# DigitalIO.net
KiCad netlist of a schematic drawn in EAGLE
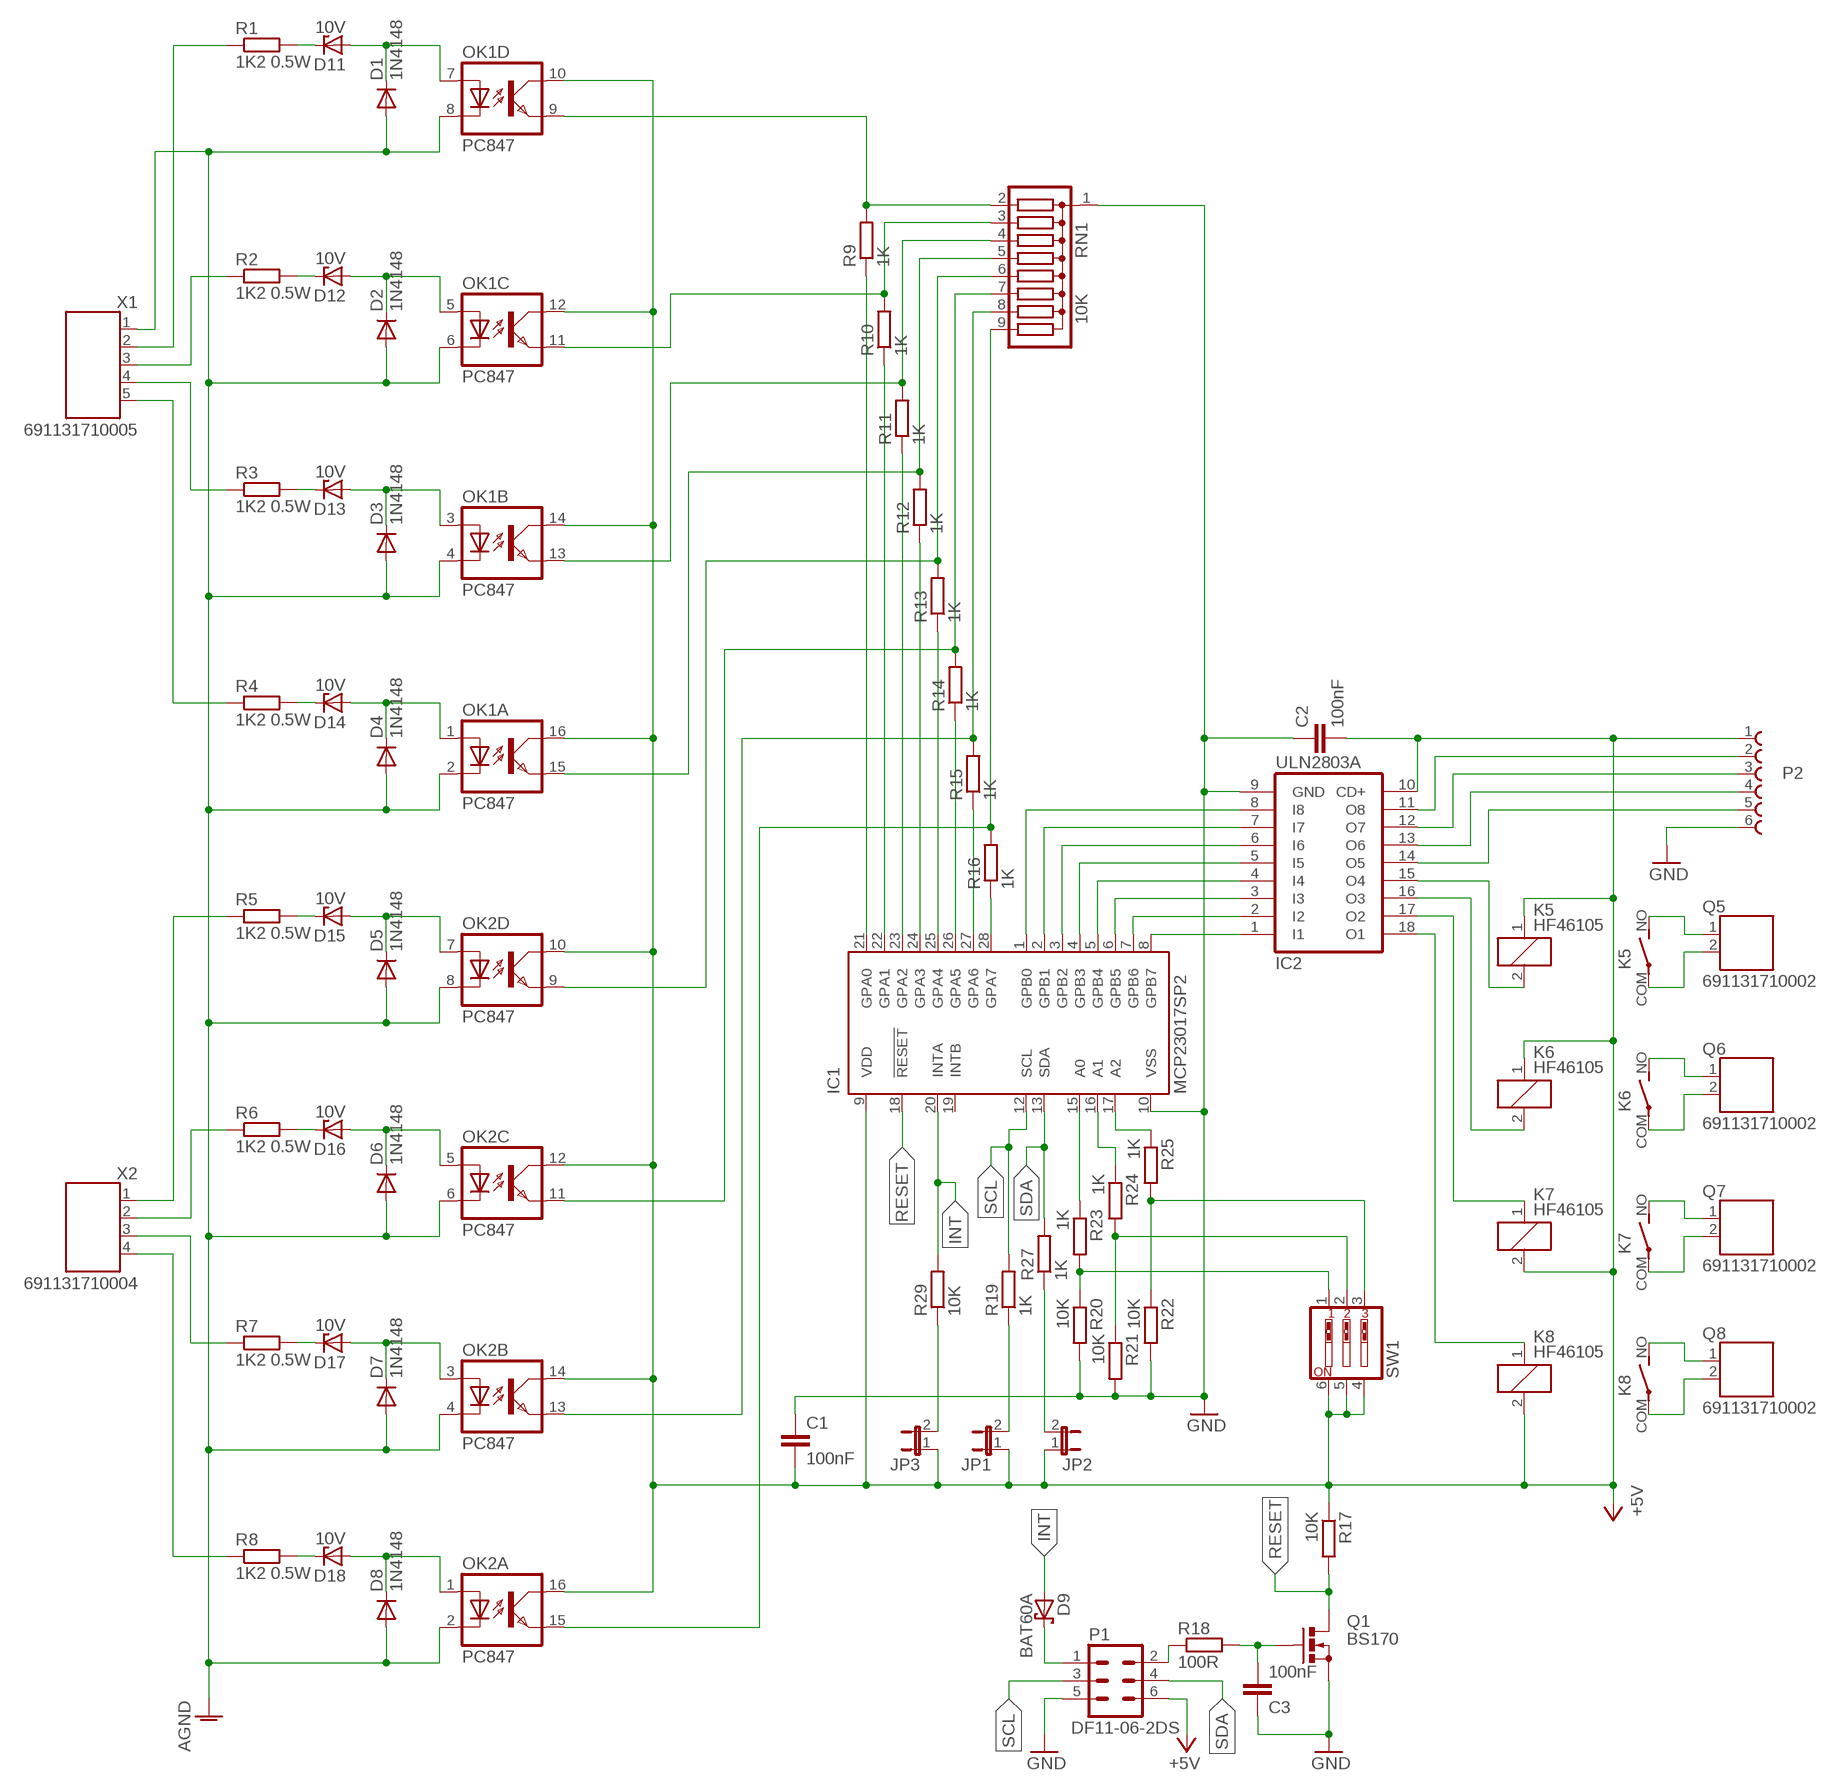
[diagram p0: schematic, sheet 1]

(export (version "E")
  (design (tool "Eeschema 10.0.6"))
  (components
    (comp (ref "C1")
      (value "100nF")
      (footprint "eagle-import:C0805")
      (fields (field (name "MF") "MULTICOMP") (field (name "MPN") "MCRR50104X7RK0050"))
      (libsource (lib "eagle-import") (part "C-EUC0805"))
    )
    (comp (ref "C2")
      (value "100nF")
      (footprint "eagle-import:C0805")
      (fields (field (name "MF") "MULTICOMP") (field (name "MPN") "MCRR50104X7RK0050"))
      (libsource (lib "eagle-import") (part "C-EUC0805"))
    )
    (comp (ref "C3")
      (value "100nF")
      (footprint "eagle-import:C0805")
      (fields (field (name "MF") "MULTICOMP") (field (name "MPN") "MCRR50104X7RK0050"))
      (libsource (lib "eagle-import") (part "C-EUC0805"))
    )
    (comp (ref "D1")
      (value "1N4148")
      (footprint "eagle-import:DO35-2V")
      (libsource (lib "eagle-import") (part "1N4148DO35-2V"))
    )
    (comp (ref "D2")
      (value "1N4148")
      (footprint "eagle-import:DO35-2V")
      (libsource (lib "eagle-import") (part "1N4148DO35-2V"))
    )
    (comp (ref "D3")
      (value "1N4148")
      (footprint "eagle-import:DO35-2V")
      (libsource (lib "eagle-import") (part "1N4148DO35-2V"))
    )
    (comp (ref "D4")
      (value "1N4148")
      (footprint "eagle-import:DO35-2V")
      (libsource (lib "eagle-import") (part "1N4148DO35-2V"))
    )
    (comp (ref "D5")
      (value "1N4148")
      (footprint "eagle-import:DO35-2V")
      (libsource (lib "eagle-import") (part "1N4148DO35-2V"))
    )
    (comp (ref "D6")
      (value "1N4148")
      (footprint "eagle-import:DO35-2V")
      (libsource (lib "eagle-import") (part "1N4148DO35-2V"))
    )
    (comp (ref "D7")
      (value "1N4148")
      (footprint "eagle-import:DO35-2V")
      (libsource (lib "eagle-import") (part "1N4148DO35-2V"))
    )
    (comp (ref "D8")
      (value "1N4148")
      (footprint "eagle-import:DO35-2V")
      (libsource (lib "eagle-import") (part "1N4148DO35-2V"))
    )
    (comp (ref "D9")
      (value "BAT60A")
      (footprint "eagle-import:SOD323_ST")
      (libsource (lib "eagle-import") (part "BAT60J"))
    )
    (comp (ref "D11")
      (value "10V")
      (footprint "eagle-import:ZDIO-2.5")
      (libsource (lib "eagle-import") (part "ZENER-DIODEZD-2.5"))
    )
    (comp (ref "D12")
      (value "10V")
      (footprint "eagle-import:ZDIO-2.5")
      (libsource (lib "eagle-import") (part "ZENER-DIODEZD-2.5"))
    )
    (comp (ref "D13")
      (value "10V")
      (footprint "eagle-import:ZDIO-2.5")
      (libsource (lib "eagle-import") (part "ZENER-DIODEZD-2.5"))
    )
    (comp (ref "D14")
      (value "10V")
      (footprint "eagle-import:ZDIO-2.5")
      (libsource (lib "eagle-import") (part "ZENER-DIODEZD-2.5"))
    )
    (comp (ref "D15")
      (value "10V")
      (footprint "eagle-import:ZDIO-2.5")
      (libsource (lib "eagle-import") (part "ZENER-DIODEZD-2.5"))
    )
    (comp (ref "D16")
      (value "10V")
      (footprint "eagle-import:ZDIO-2.5")
      (libsource (lib "eagle-import") (part "ZENER-DIODEZD-2.5"))
    )
    (comp (ref "D17")
      (value "10V")
      (footprint "eagle-import:ZDIO-2.5")
      (libsource (lib "eagle-import") (part "ZENER-DIODEZD-2.5"))
    )
    (comp (ref "D18")
      (value "10V")
      (footprint "eagle-import:ZDIO-2.5")
      (libsource (lib "eagle-import") (part "ZENER-DIODEZD-2.5"))
    )
    (comp (ref "IC1")
      (value "MCP23017SP2")
      (footprint "eagle-import:DIL28-3-ROUND")
      (libsource (lib "eagle-import") (part "MCP23017SP2"))
    )
    (comp (ref "IC2")
      (value "ULN2803A")
      (footprint "eagle-import:DIL18-ROUND")
      (fields (field (name "MF") "STMICROELECTRONICS"))
      (libsource (lib "eagle-import") (part "ULN2803ASP2"))
    )
    (comp (ref "JP1")
      (value "JP1E")
      (footprint "eagle-import:JP1")
      (libsource (lib "eagle-import") (part "JP1E"))
    )
    (comp (ref "JP2")
      (value "JP1E")
      (footprint "eagle-import:JP1")
      (libsource (lib "eagle-import") (part "JP1E"))
    )
    (comp (ref "JP3")
      (value "JP1E")
      (footprint "eagle-import:JP1")
      (libsource (lib "eagle-import") (part "JP1E"))
    )
    (comp (ref "K5")
      (value "HF46105")
      (footprint "eagle-import:HF46")
      (libsource (lib "eagle-import") (part "HF46?105"))
    )
    (comp (ref "K6")
      (value "HF46105")
      (footprint "eagle-import:HF46")
      (libsource (lib "eagle-import") (part "HF46?105"))
    )
    (comp (ref "K7")
      (value "HF46105")
      (footprint "eagle-import:HF46")
      (libsource (lib "eagle-import") (part "HF46?105"))
    )
    (comp (ref "K8")
      (value "HF46105")
      (footprint "eagle-import:HF46")
      (libsource (lib "eagle-import") (part "HF46?105"))
    )
    (comp (ref "OK1")
      (value "PC847")
      (footprint "eagle-import:DIL16")
      (libsource (lib "eagle-import") (part "PC847"))
    )
    (comp (ref "OK2")
      (value "PC847")
      (footprint "eagle-import:DIL16")
      (libsource (lib "eagle-import") (part "PC847"))
    )
    (comp (ref "P1")
      (value "DF11-06-2DS")
      (footprint "eagle-import:DF11-06DP-2DS")
      (libsource (lib "eagle-import") (part "DF11-06-2DS"))
    )
    (comp (ref "P2")
      (value "62000611121")
      (footprint "eagle-import:62000611121")
      (libsource (lib "eagle-import") (part "62000611121"))
    )
    (comp (ref "Q1")
      (value "BS170")
      (footprint "eagle-import:SOT54E")
      (libsource (lib "eagle-import") (part "BS170"))
    )
    (comp (ref "Q5")
      (value "691131710002")
      (footprint "eagle-import:691131710002")
      (libsource (lib "eagle-import") (part "691131710002"))
    )
    (comp (ref "Q6")
      (value "691131710002")
      (footprint "eagle-import:691131710002")
      (libsource (lib "eagle-import") (part "691131710002"))
    )
    (comp (ref "Q7")
      (value "691131710002")
      (footprint "eagle-import:691131710002")
      (libsource (lib "eagle-import") (part "691131710002"))
    )
    (comp (ref "Q8")
      (value "691131710002")
      (footprint "eagle-import:691131710002")
      (libsource (lib "eagle-import") (part "691131710002"))
    )
    (comp (ref "R1")
      (value "1K2 0.5W")
      (footprint "eagle-import:0207_2V")
      (fields (field (name "MF") "MULTICOMP") (field (name "MPN") "MCF 0.25W 1K2"))
      (libsource (lib "eagle-import") (part "resistor_R-EU_0207/2V"))
    )
    (comp (ref "R2")
      (value "1K2 0.5W")
      (footprint "eagle-import:0207_2V")
      (fields (field (name "MF") "MULTICOMP") (field (name "MPN") "MCF 0.25W 1K2"))
      (libsource (lib "eagle-import") (part "resistor_R-EU_0207/2V"))
    )
    (comp (ref "R3")
      (value "1K2 0.5W")
      (footprint "eagle-import:0207_2V")
      (fields (field (name "MF") "MULTICOMP") (field (name "MPN") "MCF 0.25W 1K2"))
      (libsource (lib "eagle-import") (part "resistor_R-EU_0207/2V"))
    )
    (comp (ref "R4")
      (value "1K2 0.5W")
      (footprint "eagle-import:0207_2V")
      (fields (field (name "MF") "MULTICOMP") (field (name "MPN") "MCF 0.25W 1K2"))
      (libsource (lib "eagle-import") (part "resistor_R-EU_0207/2V"))
    )
    (comp (ref "R5")
      (value "1K2 0.5W")
      (footprint "eagle-import:0207_2V")
      (fields (field (name "MF") "MULTICOMP") (field (name "MPN") "MCF 0.25W 1K2"))
      (libsource (lib "eagle-import") (part "resistor_R-EU_0207/2V"))
    )
    (comp (ref "R6")
      (value "1K2 0.5W")
      (footprint "eagle-import:0207_2V")
      (fields (field (name "MF") "MULTICOMP") (field (name "MPN") "MCF 0.25W 1K2"))
      (libsource (lib "eagle-import") (part "resistor_R-EU_0207/2V"))
    )
    (comp (ref "R7")
      (value "1K2 0.5W")
      (footprint "eagle-import:0207_2V")
      (fields (field (name "MF") "MULTICOMP") (field (name "MPN") "MCF 0.25W 1K2"))
      (libsource (lib "eagle-import") (part "resistor_R-EU_0207/2V"))
    )
    (comp (ref "R8")
      (value "1K2 0.5W")
      (footprint "eagle-import:0207_2V")
      (fields (field (name "MF") "MULTICOMP") (field (name "MPN") "MCF 0.25W 1K2"))
      (libsource (lib "eagle-import") (part "resistor_R-EU_0207/2V"))
    )
    (comp (ref "R9")
      (value "1K")
      (footprint "eagle-import:0204V")
      (libsource (lib "eagle-import") (part "resistor_R-EU_0204/2V"))
    )
    (comp (ref "R10")
      (value "1K")
      (footprint "eagle-import:0204V")
      (libsource (lib "eagle-import") (part "resistor_R-EU_0204/2V"))
    )
    (comp (ref "R11")
      (value "1K")
      (footprint "eagle-import:0204V")
      (libsource (lib "eagle-import") (part "resistor_R-EU_0204/2V"))
    )
    (comp (ref "R12")
      (value "1K")
      (footprint "eagle-import:0204V")
      (libsource (lib "eagle-import") (part "resistor_R-EU_0204/2V"))
    )
    (comp (ref "R13")
      (value "1K")
      (footprint "eagle-import:0204V")
      (libsource (lib "eagle-import") (part "resistor_R-EU_0204/2V"))
    )
    (comp (ref "R14")
      (value "1K")
      (footprint "eagle-import:0204V")
      (libsource (lib "eagle-import") (part "resistor_R-EU_0204/2V"))
    )
    (comp (ref "R15")
      (value "1K")
      (footprint "eagle-import:0204V")
      (libsource (lib "eagle-import") (part "resistor_R-EU_0204/2V"))
    )
    (comp (ref "R16")
      (value "1K")
      (footprint "eagle-import:0204V")
      (libsource (lib "eagle-import") (part "resistor_R-EU_0204/2V"))
    )
    (comp (ref "R17")
      (value "10K")
      (footprint "eagle-import:0204V")
      (libsource (lib "eagle-import") (part "resistor_R-EU_0204/2V"))
    )
    (comp (ref "R18")
      (value "100R")
      (footprint "eagle-import:0204V")
      (libsource (lib "eagle-import") (part "resistor_R-EU_0204/2V"))
    )
    (comp (ref "R19")
      (value "1K")
      (footprint "eagle-import:0204V")
      (libsource (lib "eagle-import") (part "R-EU_0204/2V"))
    )
    (comp (ref "R20")
      (value "10K")
      (footprint "eagle-import:0204V")
      (libsource (lib "eagle-import") (part "resistor_R-EU_0204/2V"))
    )
    (comp (ref "R21")
      (value "10K")
      (footprint "eagle-import:0204V")
      (libsource (lib "eagle-import") (part "resistor_R-EU_0204/2V"))
    )
    (comp (ref "R22")
      (value "10K")
      (footprint "eagle-import:0204V")
      (libsource (lib "eagle-import") (part "resistor_R-EU_0204/2V"))
    )
    (comp (ref "R23")
      (value "1K")
      (footprint "eagle-import:0204V")
      (libsource (lib "eagle-import") (part "resistor_R-EU_0204/2V"))
    )
    (comp (ref "R24")
      (value "1K")
      (footprint "eagle-import:0204V")
      (libsource (lib "eagle-import") (part "resistor_R-EU_0204/2V"))
    )
    (comp (ref "R25")
      (value "1K")
      (footprint "eagle-import:0204V")
      (libsource (lib "eagle-import") (part "resistor_R-EU_0204/2V"))
    )
    (comp (ref "R27")
      (value "1K")
      (footprint "eagle-import:0204V")
      (libsource (lib "eagle-import") (part "R-EU_0204/2V"))
    )
    (comp (ref "R29")
      (value "10K")
      (footprint "eagle-import:0204V")
      (libsource (lib "eagle-import") (part "R-EU_0204/2V"))
    )
    (comp (ref "RN1")
      (value "10K")
      (footprint "eagle-import:SIL9")
      (libsource (lib "eagle-import") (part "G08R"))
    )
    (comp (ref "SW1")
      (value "SW_DIP-3")
      (footprint "eagle-import:EDG-03")
      (libsource (lib "eagle-import") (part "SW_DIP-3"))
    )
    (comp (ref "X1")
      (value "691131710005")
      (footprint "eagle-import:691131710005")
      (libsource (lib "eagle-import") (part "691131710005"))
    )
    (comp (ref "X2")
      (value "691131710004")
      (footprint "eagle-import:691131710004")
      (libsource (lib "eagle-import") (part "691131710004"))
    )
  )
  (nets
    (net (code "1") (name "+5V") (class "Default")
      (node (ref "C1") (pin "2") (pinfunction "2_2") (pintype "passive"))
      (node (ref "C2") (pin "2") (pinfunction "2_2") (pintype "passive"))
      (node (ref "IC1") (pin "9") (pinfunction "VDD_9") (pintype "power_in"))
      (node (ref "IC2") (pin "10") (pinfunction "CD+_10") (pintype "passive"))
      (node (ref "JP1") (pin "1") (pinfunction "1_1") (pintype "passive"))
      (node (ref "JP2") (pin "1") (pinfunction "1_1") (pintype "passive"))
      (node (ref "JP3") (pin "1") (pinfunction "1_1") (pintype "passive"))
      (node (ref "K5") (pin "1") (pinfunction "1_1") (pintype "passive"))
      (node (ref "K6") (pin "1") (pinfunction "1_1") (pintype "passive"))
      (node (ref "K7") (pin "2") (pinfunction "2_2") (pintype "passive"))
      (node (ref "K8") (pin "2") (pinfunction "2_2") (pintype "passive"))
      (node (ref "OK1") (pin "10") (pinfunction "COL_10") (pintype "passive"))
      (node (ref "OK1") (pin "12") (pinfunction "COL_12") (pintype "passive"))
      (node (ref "OK1") (pin "14") (pinfunction "COL_14") (pintype "passive"))
      (node (ref "OK1") (pin "16") (pinfunction "COL_16") (pintype "passive"))
      (node (ref "OK2") (pin "10") (pinfunction "COL_10") (pintype "passive"))
      (node (ref "OK2") (pin "12") (pinfunction "COL_12") (pintype "passive"))
      (node (ref "OK2") (pin "14") (pinfunction "COL_14") (pintype "passive"))
      (node (ref "OK2") (pin "16") (pinfunction "COL_16") (pintype "passive"))
      (node (ref "P1") (pin "6") (pinfunction "6_6") (pintype "passive"))
      (node (ref "P2") (pin "1") (pinfunction "1_1") (pintype "passive"))
      (node (ref "R17") (pin "1") (pinfunction "1_1") (pintype "passive"))
      (node (ref "SW1") (pin "4") (pinfunction "4_4") (pintype "passive"))
      (node (ref "SW1") (pin "5") (pinfunction "5_5") (pintype "passive"))
      (node (ref "SW1") (pin "6") (pinfunction "6_6") (pintype "passive"))
    )
    (net (code "2") (name "AGND") (class "Default")
      (node (ref "D1") (pin "A") (pinfunction "A_A") (pintype "passive"))
      (node (ref "D2") (pin "A") (pinfunction "A_A") (pintype "passive"))
      (node (ref "D3") (pin "A") (pinfunction "A_A") (pintype "passive"))
      (node (ref "D4") (pin "A") (pinfunction "A_A") (pintype "passive"))
      (node (ref "D5") (pin "A") (pinfunction "A_A") (pintype "passive"))
      (node (ref "D6") (pin "A") (pinfunction "A_A") (pintype "passive"))
      (node (ref "D7") (pin "A") (pinfunction "A_A") (pintype "passive"))
      (node (ref "D8") (pin "A") (pinfunction "A_A") (pintype "passive"))
      (node (ref "OK1") (pin "2") (pinfunction "C_2") (pintype "passive"))
      (node (ref "OK1") (pin "4") (pinfunction "C_4") (pintype "passive"))
      (node (ref "OK1") (pin "6") (pinfunction "C_6") (pintype "passive"))
      (node (ref "OK1") (pin "8") (pinfunction "C_8") (pintype "passive"))
      (node (ref "OK2") (pin "2") (pinfunction "C_2") (pintype "passive"))
      (node (ref "OK2") (pin "4") (pinfunction "C_4") (pintype "passive"))
      (node (ref "OK2") (pin "6") (pinfunction "C_6") (pintype "passive"))
      (node (ref "OK2") (pin "8") (pinfunction "C_8") (pintype "passive"))
      (node (ref "X1") (pin "1") (pinfunction "1_1") (pintype "passive"))
    )
    (net (code "3") (name "GND") (class "Default")
      (node (ref "C1") (pin "1") (pinfunction "1_1") (pintype "passive"))
      (node (ref "C2") (pin "1") (pinfunction "1_1") (pintype "passive"))
      (node (ref "C3") (pin "1") (pinfunction "1_1") (pintype "passive"))
      (node (ref "IC1") (pin "10") (pinfunction "VSS_10") (pintype "power_in"))
      (node (ref "IC2") (pin "9") (pinfunction "GND_9") (pintype "power_in"))
      (node (ref "P1") (pin "5") (pinfunction "5_5") (pintype "passive"))
      (node (ref "P2") (pin "6") (pinfunction "6_6") (pintype "passive"))
      (node (ref "Q1") (pin "S") (pinfunction "S_S") (pintype "passive"))
      (node (ref "R20") (pin "2") (pinfunction "2_2") (pintype "passive"))
      (node (ref "R21") (pin "2") (pinfunction "2_2") (pintype "passive"))
      (node (ref "R22") (pin "2") (pinfunction "2_2") (pintype "passive"))
      (node (ref "RN1") (pin "1") (pinfunction "1_1") (pintype "passive"))
    )
    (net (code "4") (name "INT") (class "Default")
      (node (ref "D9") (pin "A") (pinfunction "A_A") (pintype "passive"))
      (node (ref "IC1") (pin "20") (pinfunction "INTA_20") (pintype "output"))
      (node (ref "R29") (pin "2") (pinfunction "2_2") (pintype "passive"))
    )
    (net (code "5") (name "Net-(C3-Pad2)") (class "Default")
      (node (ref "C3") (pin "2") (pinfunction "2_2") (pintype "passive"))
      (node (ref "Q1") (pin "G") (pinfunction "G_G") (pintype "passive"))
      (node (ref "R18") (pin "2") (pinfunction "2_2") (pintype "passive"))
    )
    (net (code "6") (name "Net-(D9-PadC)") (class "Default")
      (node (ref "D9") (pin "C") (pinfunction "C_C") (pintype "passive"))
      (node (ref "P1") (pin "1") (pinfunction "1_1") (pintype "passive"))
    )
    (net (code "7") (name "Net-(D11-PadC)") (class "Default")
      (node (ref "D11") (pin "C") (pinfunction "C_C") (pintype "passive"))
      (node (ref "R1") (pin "2") (pinfunction "2_2") (pintype "passive"))
    )
    (net (code "8") (name "Net-(D12-PadC)") (class "Default")
      (node (ref "D12") (pin "C") (pinfunction "C_C") (pintype "passive"))
      (node (ref "R2") (pin "2") (pinfunction "2_2") (pintype "passive"))
    )
    (net (code "9") (name "Net-(D13-PadC)") (class "Default")
      (node (ref "D13") (pin "C") (pinfunction "C_C") (pintype "passive"))
      (node (ref "R3") (pin "2") (pinfunction "2_2") (pintype "passive"))
    )
    (net (code "10") (name "Net-(D14-PadC)") (class "Default")
      (node (ref "D14") (pin "C") (pinfunction "C_C") (pintype "passive"))
      (node (ref "R4") (pin "2") (pinfunction "2_2") (pintype "passive"))
    )
    (net (code "11") (name "Net-(D15-PadC)") (class "Default")
      (node (ref "D15") (pin "C") (pinfunction "C_C") (pintype "passive"))
      (node (ref "R5") (pin "2") (pinfunction "2_2") (pintype "passive"))
    )
    (net (code "12") (name "Net-(D16-PadC)") (class "Default")
      (node (ref "D16") (pin "C") (pinfunction "C_C") (pintype "passive"))
      (node (ref "R6") (pin "2") (pinfunction "2_2") (pintype "passive"))
    )
    (net (code "13") (name "Net-(D17-PadC)") (class "Default")
      (node (ref "D17") (pin "C") (pinfunction "C_C") (pintype "passive"))
      (node (ref "R7") (pin "2") (pinfunction "2_2") (pintype "passive"))
    )
    (net (code "14") (name "Net-(D18-PadC)") (class "Default")
      (node (ref "D18") (pin "C") (pinfunction "C_C") (pintype "passive"))
      (node (ref "R8") (pin "2") (pinfunction "2_2") (pintype "passive"))
    )
    (net (code "15") (name "Net-(IC1-A0)") (class "Default")
      (node (ref "IC1") (pin "15") (pinfunction "A0_15") (pintype "input"))
      (node (ref "R23") (pin "1") (pinfunction "1_1") (pintype "passive"))
    )
    (net (code "16") (name "Net-(IC1-A1)") (class "Default")
      (node (ref "IC1") (pin "16") (pinfunction "A1_16") (pintype "input"))
      (node (ref "R24") (pin "1") (pinfunction "1_1") (pintype "passive"))
    )
    (net (code "17") (name "Net-(IC1-A2)") (class "Default")
      (node (ref "IC1") (pin "17") (pinfunction "A2_17") (pintype "input"))
      (node (ref "R25") (pin "1") (pinfunction "1_1") (pintype "passive"))
    )
    (net (code "18") (name "Net-(IC1-GPA0)") (class "Default")
      (node (ref "IC1") (pin "21") (pinfunction "GPA0_21") (pintype "bidirectional"))
      (node (ref "R9") (pin "1") (pinfunction "1_1") (pintype "passive"))
    )
    (net (code "19") (name "Net-(IC1-GPA1)") (class "Default")
      (node (ref "IC1") (pin "22") (pinfunction "GPA1_22") (pintype "bidirectional"))
      (node (ref "R10") (pin "1") (pinfunction "1_1") (pintype "passive"))
    )
    (net (code "20") (name "Net-(IC1-GPA2)") (class "Default")
      (node (ref "IC1") (pin "23") (pinfunction "GPA2_23") (pintype "bidirectional"))
      (node (ref "R11") (pin "1") (pinfunction "1_1") (pintype "passive"))
    )
    (net (code "21") (name "Net-(IC1-GPA3)") (class "Default")
      (node (ref "IC1") (pin "24") (pinfunction "GPA3_24") (pintype "bidirectional"))
      (node (ref "R12") (pin "1") (pinfunction "1_1") (pintype "passive"))
    )
    (net (code "22") (name "Net-(IC1-GPA4)") (class "Default")
      (node (ref "IC1") (pin "25") (pinfunction "GPA4_25") (pintype "bidirectional"))
      (node (ref "R13") (pin "1") (pinfunction "1_1") (pintype "passive"))
    )
    (net (code "23") (name "Net-(IC1-GPA5)") (class "Default")
      (node (ref "IC1") (pin "26") (pinfunction "GPA5_26") (pintype "bidirectional"))
      (node (ref "R14") (pin "1") (pinfunction "1_1") (pintype "passive"))
    )
    (net (code "24") (name "Net-(IC1-GPA6)") (class "Default")
      (node (ref "IC1") (pin "27") (pinfunction "GPA6_27") (pintype "bidirectional"))
      (node (ref "R15") (pin "1") (pinfunction "1_1") (pintype "passive"))
    )
    (net (code "25") (name "Net-(IC1-GPA7)") (class "Default")
      (node (ref "IC1") (pin "28") (pinfunction "GPA7_28") (pintype "bidirectional"))
      (node (ref "R16") (pin "1") (pinfunction "1_1") (pintype "passive"))
    )
    (net (code "26") (name "Net-(IC1-GPB0)") (class "Default")
      (node (ref "IC1") (pin "1") (pinfunction "GPB0_1") (pintype "bidirectional"))
      (node (ref "IC2") (pin "8") (pinfunction "I8_8") (pintype "input"))
    )
    (net (code "27") (name "Net-(IC1-GPB1)") (class "Default")
      (node (ref "IC1") (pin "2") (pinfunction "GPB1_2") (pintype "bidirectional"))
      (node (ref "IC2") (pin "7") (pinfunction "I7_7") (pintype "input"))
    )
    (net (code "28") (name "Net-(IC1-GPB2)") (class "Default")
      (node (ref "IC1") (pin "3") (pinfunction "GPB2_3") (pintype "bidirectional"))
      (node (ref "IC2") (pin "6") (pinfunction "I6_6") (pintype "input"))
    )
    (net (code "29") (name "Net-(IC1-GPB3)") (class "Default")
      (node (ref "IC1") (pin "4") (pinfunction "GPB3_4") (pintype "bidirectional"))
      (node (ref "IC2") (pin "5") (pinfunction "I5_5") (pintype "input"))
    )
    (net (code "30") (name "Net-(IC1-GPB4)") (class "Default")
      (node (ref "IC1") (pin "5") (pinfunction "GPB4_5") (pintype "bidirectional"))
      (node (ref "IC2") (pin "4") (pinfunction "I4_4") (pintype "input"))
    )
    (net (code "31") (name "Net-(IC1-GPB5)") (class "Default")
      (node (ref "IC1") (pin "6") (pinfunction "GPB5_6") (pintype "bidirectional"))
      (node (ref "IC2") (pin "3") (pinfunction "I3_3") (pintype "input"))
    )
    (net (code "32") (name "Net-(IC1-GPB6)") (class "Default")
      (node (ref "IC1") (pin "7") (pinfunction "GPB6_7") (pintype "bidirectional"))
      (node (ref "IC2") (pin "2") (pinfunction "I2_2") (pintype "input"))
    )
    (net (code "33") (name "Net-(IC1-GPB7)") (class "Default")
      (node (ref "IC1") (pin "8") (pinfunction "GPB7_8") (pintype "bidirectional"))
      (node (ref "IC2") (pin "1") (pinfunction "I1_1") (pintype "input"))
    )
    (net (code "34") (name "Net-(IC2-O1)") (class "Default")
      (node (ref "IC2") (pin "18") (pinfunction "O1_18") (pintype "open_collector"))
      (node (ref "K8") (pin "1") (pinfunction "1_1") (pintype "passive"))
    )
    (net (code "35") (name "Net-(IC2-O2)") (class "Default")
      (node (ref "IC2") (pin "17") (pinfunction "O2_17") (pintype "open_collector"))
      (node (ref "K7") (pin "1") (pinfunction "1_1") (pintype "passive"))
    )
    (net (code "36") (name "Net-(IC2-O3)") (class "Default")
      (node (ref "IC2") (pin "16") (pinfunction "O3_16") (pintype "open_collector"))
      (node (ref "K6") (pin "2") (pinfunction "2_2") (pintype "passive"))
    )
    (net (code "37") (name "Net-(IC2-O4)") (class "Default")
      (node (ref "IC2") (pin "15") (pinfunction "O4_15") (pintype "open_collector"))
      (node (ref "K5") (pin "2") (pinfunction "2_2") (pintype "passive"))
    )
    (net (code "38") (name "Net-(IC2-O5)") (class "Default")
      (node (ref "IC2") (pin "14") (pinfunction "O5_14") (pintype "open_collector"))
      (node (ref "P2") (pin "5") (pinfunction "5_5") (pintype "passive"))
    )
    (net (code "39") (name "Net-(IC2-O6)") (class "Default")
      (node (ref "IC2") (pin "13") (pinfunction "O6_13") (pintype "open_collector"))
      (node (ref "P2") (pin "4") (pinfunction "4_4") (pintype "passive"))
    )
    (net (code "40") (name "Net-(IC2-O7)") (class "Default")
      (node (ref "IC2") (pin "12") (pinfunction "O7_12") (pintype "open_collector"))
      (node (ref "P2") (pin "3") (pinfunction "3_3") (pintype "passive"))
    )
    (net (code "41") (name "Net-(IC2-O8)") (class "Default")
      (node (ref "IC2") (pin "11") (pinfunction "O8_11") (pintype "open_collector"))
      (node (ref "P2") (pin "2") (pinfunction "2_2") (pintype "passive"))
    )
    (net (code "42") (name "Net-(JP1-Pad2)") (class "Default")
      (node (ref "JP1") (pin "2") (pinfunction "2_2") (pintype "passive"))
      (node (ref "R19") (pin "1") (pinfunction "1_1") (pintype "passive"))
    )
    (net (code "43") (name "Net-(JP2-Pad2)") (class "Default")
      (node (ref "JP2") (pin "2") (pinfunction "2_2") (pintype "passive"))
      (node (ref "R27") (pin "1") (pinfunction "1_1") (pintype "passive"))
    )
    (net (code "44") (name "Net-(JP3-Pad2)") (class "Default")
      (node (ref "JP3") (pin "2") (pinfunction "2_2") (pintype "passive"))
      (node (ref "R29") (pin "1") (pinfunction "1_1") (pintype "passive"))
    )
    (net (code "45") (name "Net-(K5B-P)") (class "Default")
      (node (ref "K5") (pin "COM") (pinfunction "P_COM") (pintype "passive"))
      (node (ref "Q5") (pin "2") (pinfunction "2_2") (pintype "passive"))
    )
    (net (code "46") (name "Net-(K5B-S)") (class "Default")
      (node (ref "K5") (pin "NO") (pinfunction "S_NO") (pintype "passive"))
      (node (ref "Q5") (pin "1") (pinfunction "1_1") (pintype "passive"))
    )
    (net (code "47") (name "Net-(K6B-P)") (class "Default")
      (node (ref "K6") (pin "COM") (pinfunction "P_COM") (pintype "passive"))
      (node (ref "Q6") (pin "2") (pinfunction "2_2") (pintype "passive"))
    )
    (net (code "48") (name "Net-(K6B-S)") (class "Default")
      (node (ref "K6") (pin "NO") (pinfunction "S_NO") (pintype "passive"))
      (node (ref "Q6") (pin "1") (pinfunction "1_1") (pintype "passive"))
    )
    (net (code "49") (name "Net-(K7B-P)") (class "Default")
      (node (ref "K7") (pin "COM") (pinfunction "P_COM") (pintype "passive"))
      (node (ref "Q7") (pin "2") (pinfunction "2_2") (pintype "passive"))
    )
    (net (code "50") (name "Net-(K7B-S)") (class "Default")
      (node (ref "K7") (pin "NO") (pinfunction "S_NO") (pintype "passive"))
      (node (ref "Q7") (pin "1") (pinfunction "1_1") (pintype "passive"))
    )
    (net (code "51") (name "Net-(K8B-P)") (class "Default")
      (node (ref "K8") (pin "COM") (pinfunction "P_COM") (pintype "passive"))
      (node (ref "Q8") (pin "2") (pinfunction "2_2") (pintype "passive"))
    )
    (net (code "52") (name "Net-(K8B-S)") (class "Default")
      (node (ref "K8") (pin "NO") (pinfunction "S_NO") (pintype "passive"))
      (node (ref "Q8") (pin "1") (pinfunction "1_1") (pintype "passive"))
    )
    (net (code "53") (name "Net-(OK1A-A)") (class "Default")
      (node (ref "D14") (pin "A") (pinfunction "A_A") (pintype "passive"))
      (node (ref "D4") (pin "C") (pinfunction "C_C") (pintype "passive"))
      (node (ref "OK1") (pin "1") (pinfunction "A_1") (pintype "passive"))
    )
    (net (code "54") (name "Net-(OK1A-EMIT)") (class "Default")
      (node (ref "OK1") (pin "15") (pinfunction "EMIT_15") (pintype "passive"))
      (node (ref "R12") (pin "2") (pinfunction "2_2") (pintype "passive"))
      (node (ref "RN1") (pin "5") (pinfunction "5_5") (pintype "passive"))
    )
    (net (code "55") (name "Net-(OK1B-A)") (class "Default")
      (node (ref "D13") (pin "A") (pinfunction "A_A") (pintype "passive"))
      (node (ref "D3") (pin "C") (pinfunction "C_C") (pintype "passive"))
      (node (ref "OK1") (pin "3") (pinfunction "A_3") (pintype "passive"))
    )
    (net (code "56") (name "Net-(OK1B-EMIT)") (class "Default")
      (node (ref "OK1") (pin "13") (pinfunction "EMIT_13") (pintype "passive"))
      (node (ref "R11") (pin "2") (pinfunction "2_2") (pintype "passive"))
      (node (ref "RN1") (pin "4") (pinfunction "4_4") (pintype "passive"))
    )
    (net (code "57") (name "Net-(OK1C-A)") (class "Default")
      (node (ref "D12") (pin "A") (pinfunction "A_A") (pintype "passive"))
      (node (ref "D2") (pin "C") (pinfunction "C_C") (pintype "passive"))
      (node (ref "OK1") (pin "5") (pinfunction "A_5") (pintype "passive"))
    )
    (net (code "58") (name "Net-(OK1C-EMIT)") (class "Default")
      (node (ref "OK1") (pin "11") (pinfunction "EMIT_11") (pintype "passive"))
      (node (ref "R10") (pin "2") (pinfunction "2_2") (pintype "passive"))
      (node (ref "RN1") (pin "3") (pinfunction "3_3") (pintype "passive"))
    )
    (net (code "59") (name "Net-(OK1D-A)") (class "Default")
      (node (ref "D1") (pin "C") (pinfunction "C_C") (pintype "passive"))
      (node (ref "D11") (pin "A") (pinfunction "A_A") (pintype "passive"))
      (node (ref "OK1") (pin "7") (pinfunction "A_7") (pintype "passive"))
    )
    (net (code "60") (name "Net-(OK1D-EMIT)") (class "Default")
      (node (ref "OK1") (pin "9") (pinfunction "EMIT_9") (pintype "passive"))
      (node (ref "R9") (pin "2") (pinfunction "2_2") (pintype "passive"))
      (node (ref "RN1") (pin "2") (pinfunction "2_2") (pintype "passive"))
    )
    (net (code "61") (name "Net-(OK2A-A)") (class "Default")
      (node (ref "D18") (pin "A") (pinfunction "A_A") (pintype "passive"))
      (node (ref "D8") (pin "C") (pinfunction "C_C") (pintype "passive"))
      (node (ref "OK2") (pin "1") (pinfunction "A_1") (pintype "passive"))
    )
    (net (code "62") (name "Net-(OK2A-EMIT)") (class "Default")
      (node (ref "OK2") (pin "15") (pinfunction "EMIT_15") (pintype "passive"))
      (node (ref "R16") (pin "2") (pinfunction "2_2") (pintype "passive"))
      (node (ref "RN1") (pin "9") (pinfunction "9_9") (pintype "passive"))
    )
    (net (code "63") (name "Net-(OK2B-A)") (class "Default")
      (node (ref "D17") (pin "A") (pinfunction "A_A") (pintype "passive"))
      (node (ref "D7") (pin "C") (pinfunction "C_C") (pintype "passive"))
      (node (ref "OK2") (pin "3") (pinfunction "A_3") (pintype "passive"))
    )
    (net (code "64") (name "Net-(OK2B-EMIT)") (class "Default")
      (node (ref "OK2") (pin "13") (pinfunction "EMIT_13") (pintype "passive"))
      (node (ref "R15") (pin "2") (pinfunction "2_2") (pintype "passive"))
      (node (ref "RN1") (pin "8") (pinfunction "8_8") (pintype "passive"))
    )
    (net (code "65") (name "Net-(OK2C-A)") (class "Default")
      (node (ref "D16") (pin "A") (pinfunction "A_A") (pintype "passive"))
      (node (ref "D6") (pin "C") (pinfunction "C_C") (pintype "passive"))
      (node (ref "OK2") (pin "5") (pinfunction "A_5") (pintype "passive"))
    )
    (net (code "66") (name "Net-(OK2C-EMIT)") (class "Default")
      (node (ref "OK2") (pin "11") (pinfunction "EMIT_11") (pintype "passive"))
      (node (ref "R14") (pin "2") (pinfunction "2_2") (pintype "passive"))
      (node (ref "RN1") (pin "7") (pinfunction "7_7") (pintype "passive"))
    )
    (net (code "67") (name "Net-(OK2D-A)") (class "Default")
      (node (ref "D15") (pin "A") (pinfunction "A_A") (pintype "passive"))
      (node (ref "D5") (pin "C") (pinfunction "C_C") (pintype "passive"))
      (node (ref "OK2") (pin "7") (pinfunction "A_7") (pintype "passive"))
    )
    (net (code "68") (name "Net-(OK2D-EMIT)") (class "Default")
      (node (ref "OK2") (pin "9") (pinfunction "EMIT_9") (pintype "passive"))
      (node (ref "R13") (pin "2") (pinfunction "2_2") (pintype "passive"))
      (node (ref "RN1") (pin "6") (pinfunction "6_6") (pintype "passive"))
    )
    (net (code "69") (name "Net-(P1-Pad2)") (class "Default")
      (node (ref "P1") (pin "2") (pinfunction "2_2") (pintype "passive"))
      (node (ref "R18") (pin "1") (pinfunction "1_1") (pintype "passive"))
    )
    (net (code "70") (name "Net-(R1-Pad1)") (class "Default")
      (node (ref "R1") (pin "1") (pinfunction "1_1") (pintype "passive"))
      (node (ref "X1") (pin "2") (pinfunction "2_2") (pintype "passive"))
    )
    (net (code "71") (name "Net-(R2-Pad1)") (class "Default")
      (node (ref "R2") (pin "1") (pinfunction "1_1") (pintype "passive"))
      (node (ref "X1") (pin "3") (pinfunction "3_3") (pintype "passive"))
    )
    (net (code "72") (name "Net-(R3-Pad1)") (class "Default")
      (node (ref "R3") (pin "1") (pinfunction "1_1") (pintype "passive"))
      (node (ref "X1") (pin "4") (pinfunction "4_4") (pintype "passive"))
    )
    (net (code "73") (name "Net-(R4-Pad1)") (class "Default")
      (node (ref "R4") (pin "1") (pinfunction "1_1") (pintype "passive"))
      (node (ref "X1") (pin "5") (pinfunction "5_5") (pintype "passive"))
    )
    (net (code "74") (name "Net-(R5-Pad1)") (class "Default")
      (node (ref "R5") (pin "1") (pinfunction "1_1") (pintype "passive"))
      (node (ref "X2") (pin "1") (pinfunction "1_1") (pintype "passive"))
    )
    (net (code "75") (name "Net-(R6-Pad1)") (class "Default")
      (node (ref "R6") (pin "1") (pinfunction "1_1") (pintype "passive"))
      (node (ref "X2") (pin "2") (pinfunction "2_2") (pintype "passive"))
    )
    (net (code "76") (name "Net-(R7-Pad1)") (class "Default")
      (node (ref "R7") (pin "1") (pinfunction "1_1") (pintype "passive"))
      (node (ref "X2") (pin "3") (pinfunction "3_3") (pintype "passive"))
    )
    (net (code "77") (name "Net-(R8-Pad1)") (class "Default")
      (node (ref "R8") (pin "1") (pinfunction "1_1") (pintype "passive"))
      (node (ref "X2") (pin "4") (pinfunction "4_4") (pintype "passive"))
    )
    (net (code "78") (name "Net-(R20-Pad1)") (class "Default")
      (node (ref "R20") (pin "1") (pinfunction "1_1") (pintype "passive"))
      (node (ref "R23") (pin "2") (pinfunction "2_2") (pintype "passive"))
      (node (ref "SW1") (pin "1") (pinfunction "1_1") (pintype "passive"))
    )
    (net (code "79") (name "Net-(R21-Pad1)") (class "Default")
      (node (ref "R21") (pin "1") (pinfunction "1_1") (pintype "passive"))
      (node (ref "R24") (pin "2") (pinfunction "2_2") (pintype "passive"))
      (node (ref "SW1") (pin "2") (pinfunction "2_2") (pintype "passive"))
    )
    (net (code "80") (name "Net-(R22-Pad1)") (class "Default")
      (node (ref "R22") (pin "1") (pinfunction "1_1") (pintype "passive"))
      (node (ref "R25") (pin "2") (pinfunction "2_2") (pintype "passive"))
      (node (ref "SW1") (pin "3") (pinfunction "3_3") (pintype "passive"))
    )
    (net (code "81") (name "RESET") (class "Default")
      (node (ref "IC1") (pin "18") (pinfunction "~{RESET}_18") (pintype "input"))
      (node (ref "Q1") (pin "D") (pinfunction "D_D") (pintype "passive"))
      (node (ref "R17") (pin "2") (pinfunction "2_2") (pintype "passive"))
    )
    (net (code "82") (name "SCL") (class "Default")
      (node (ref "IC1") (pin "12") (pinfunction "SCL_12") (pintype "input"))
      (node (ref "P1") (pin "3") (pinfunction "3_3") (pintype "passive"))
      (node (ref "R19") (pin "2") (pinfunction "2_2") (pintype "passive"))
    )
    (net (code "83") (name "SDA") (class "Default")
      (node (ref "IC1") (pin "13") (pinfunction "SDA_13") (pintype "bidirectional"))
      (node (ref "P1") (pin "4") (pinfunction "4_4") (pintype "passive"))
      (node (ref "R27") (pin "2") (pinfunction "2_2") (pintype "passive"))
    )
    (net (code "84") (name "unconnected-(IC1-INTB-Pad19)") (class "Default")
      (node (ref "IC1") (pin "19") (pinfunction "INTB_19") (pintype "output"))
    )
  )
)
